# InnerMaskFinal.net
KiCad netlist of a schematic drawn in Altium Designer
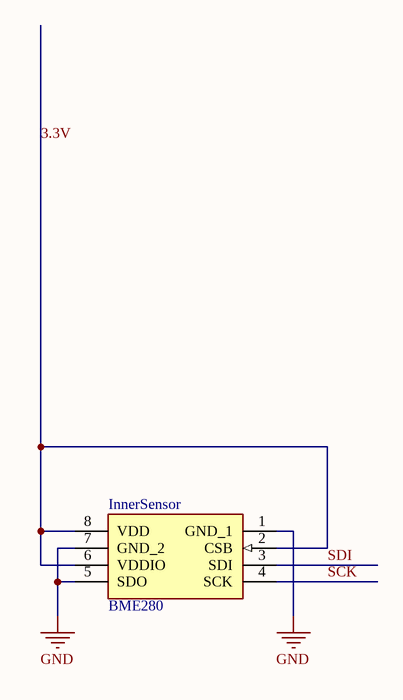
[diagram p0: InnerMaskFinal.SchDoc]

(export (version "E")
  (design (tool "Eeschema 10.0.6"))
  (components
    (comp (ref "InnerSensor")
      (value "BME280")
      (footprint "SamacSys:BME280")
      (description "Hygrometer")
      (fields (field (name "MOUSER PART NUMBER") "262-BME280"))
      (libsource (lib "*") (part "BME280"))
    )
  )
  (nets
    (net (code "1") (name "/3.3V") (class "Default")
      (node (ref "InnerSensor") (pin "2") (pinfunction "CSB_2") (pintype "input"))
      (node (ref "InnerSensor") (pin "6") (pinfunction "VDDIO_6") (pintype "power_in"))
      (node (ref "InnerSensor") (pin "8") (pinfunction "VDD_8") (pintype "power_in"))
    )
    (net (code "2") (name "/SCK") (class "Default")
      (node (ref "InnerSensor") (pin "4") (pinfunction "SCK_4") (pintype "passive"))
    )
    (net (code "3") (name "/SDI") (class "Default")
      (node (ref "InnerSensor") (pin "3") (pinfunction "SDI_3") (pintype "passive"))
    )
    (net (code "4") (name "GND") (class "Default")
      (node (ref "InnerSensor") (pin "1") (pinfunction "GND_1_1") (pintype "power_in"))
      (node (ref "InnerSensor") (pin "5") (pinfunction "SDO_5") (pintype "passive"))
      (node (ref "InnerSensor") (pin "7") (pinfunction "GND_2_7") (pintype "power_in"))
    )
  )
)
